# PWR_MGMT.net
KiCad netlist of a schematic drawn in Altium Designer
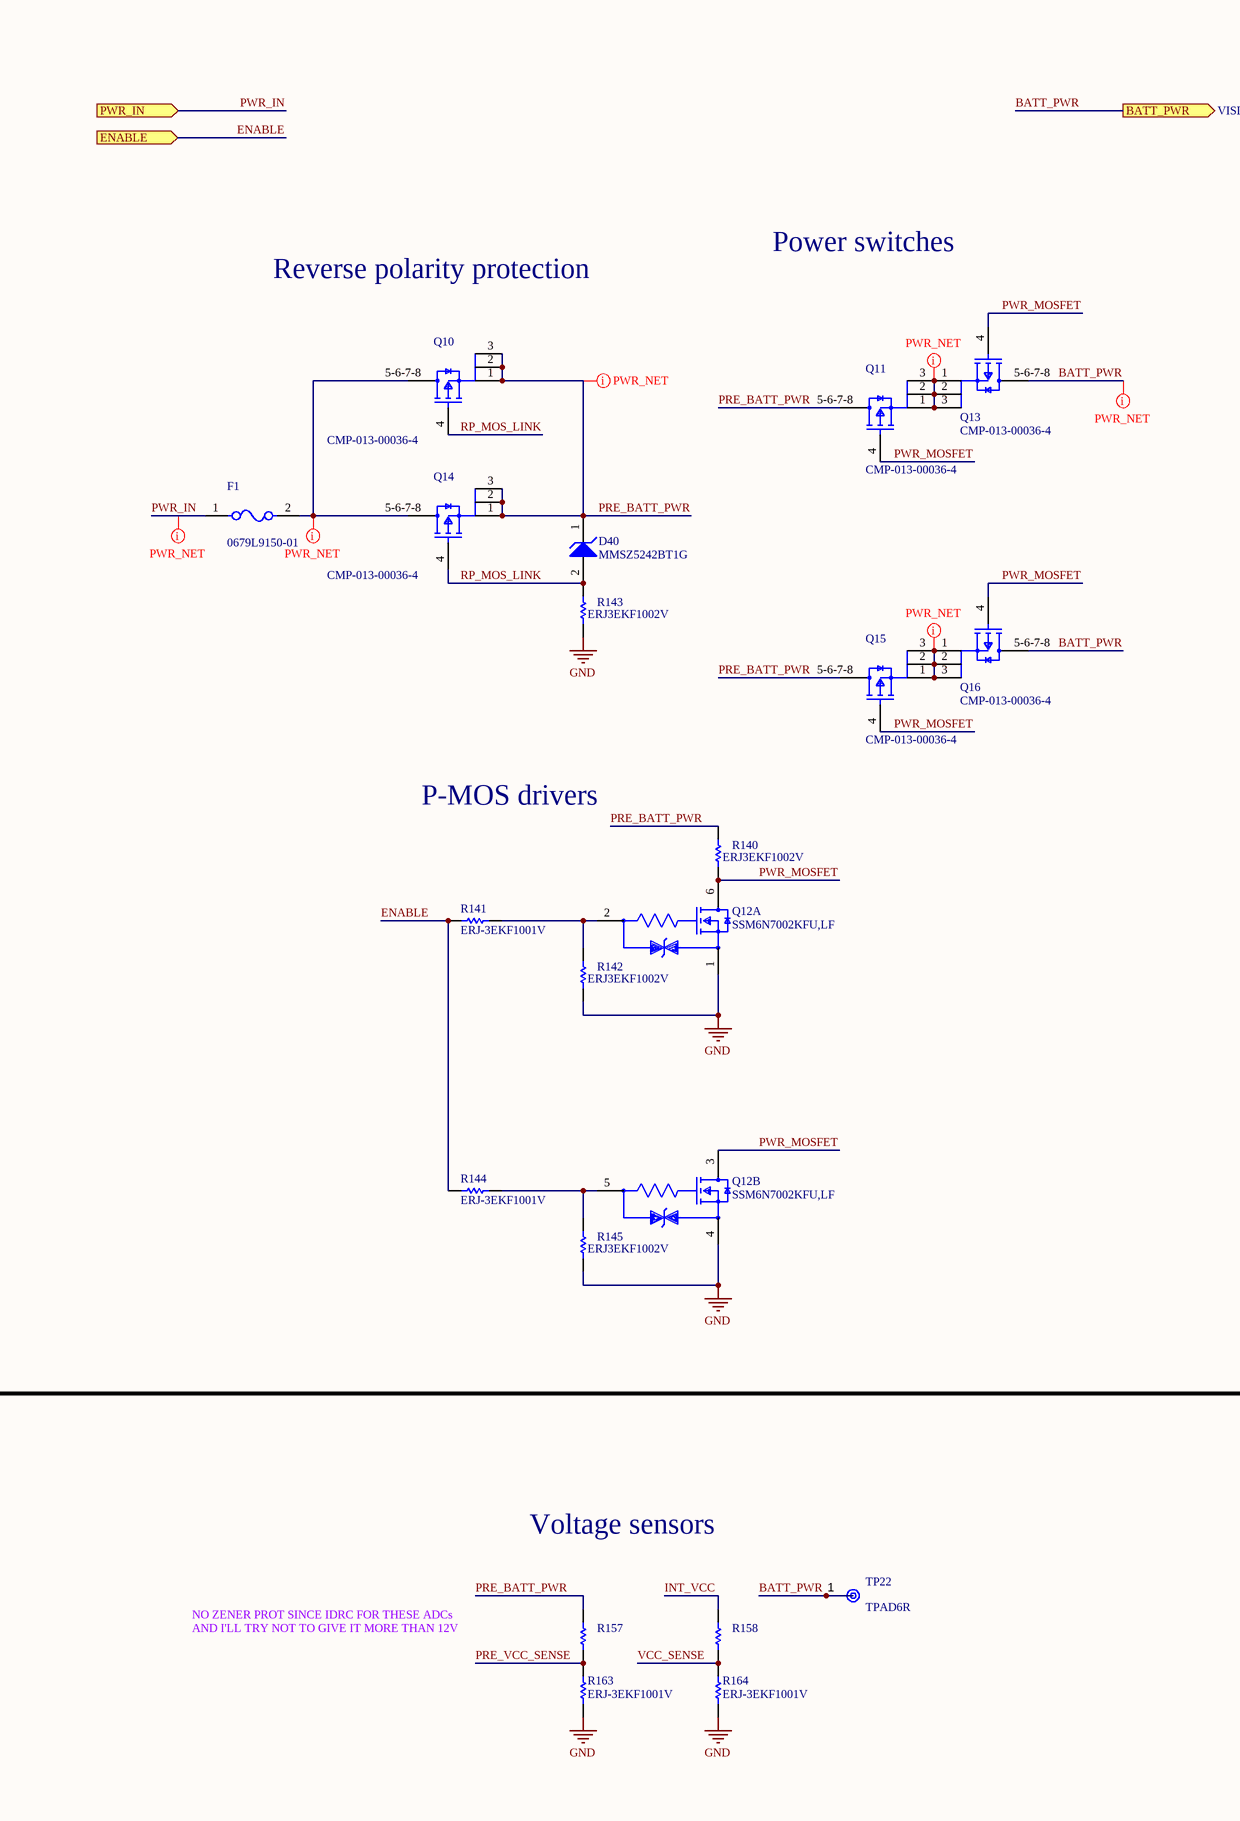
[diagram p0: PWR_MGMT.SchDoc, left]
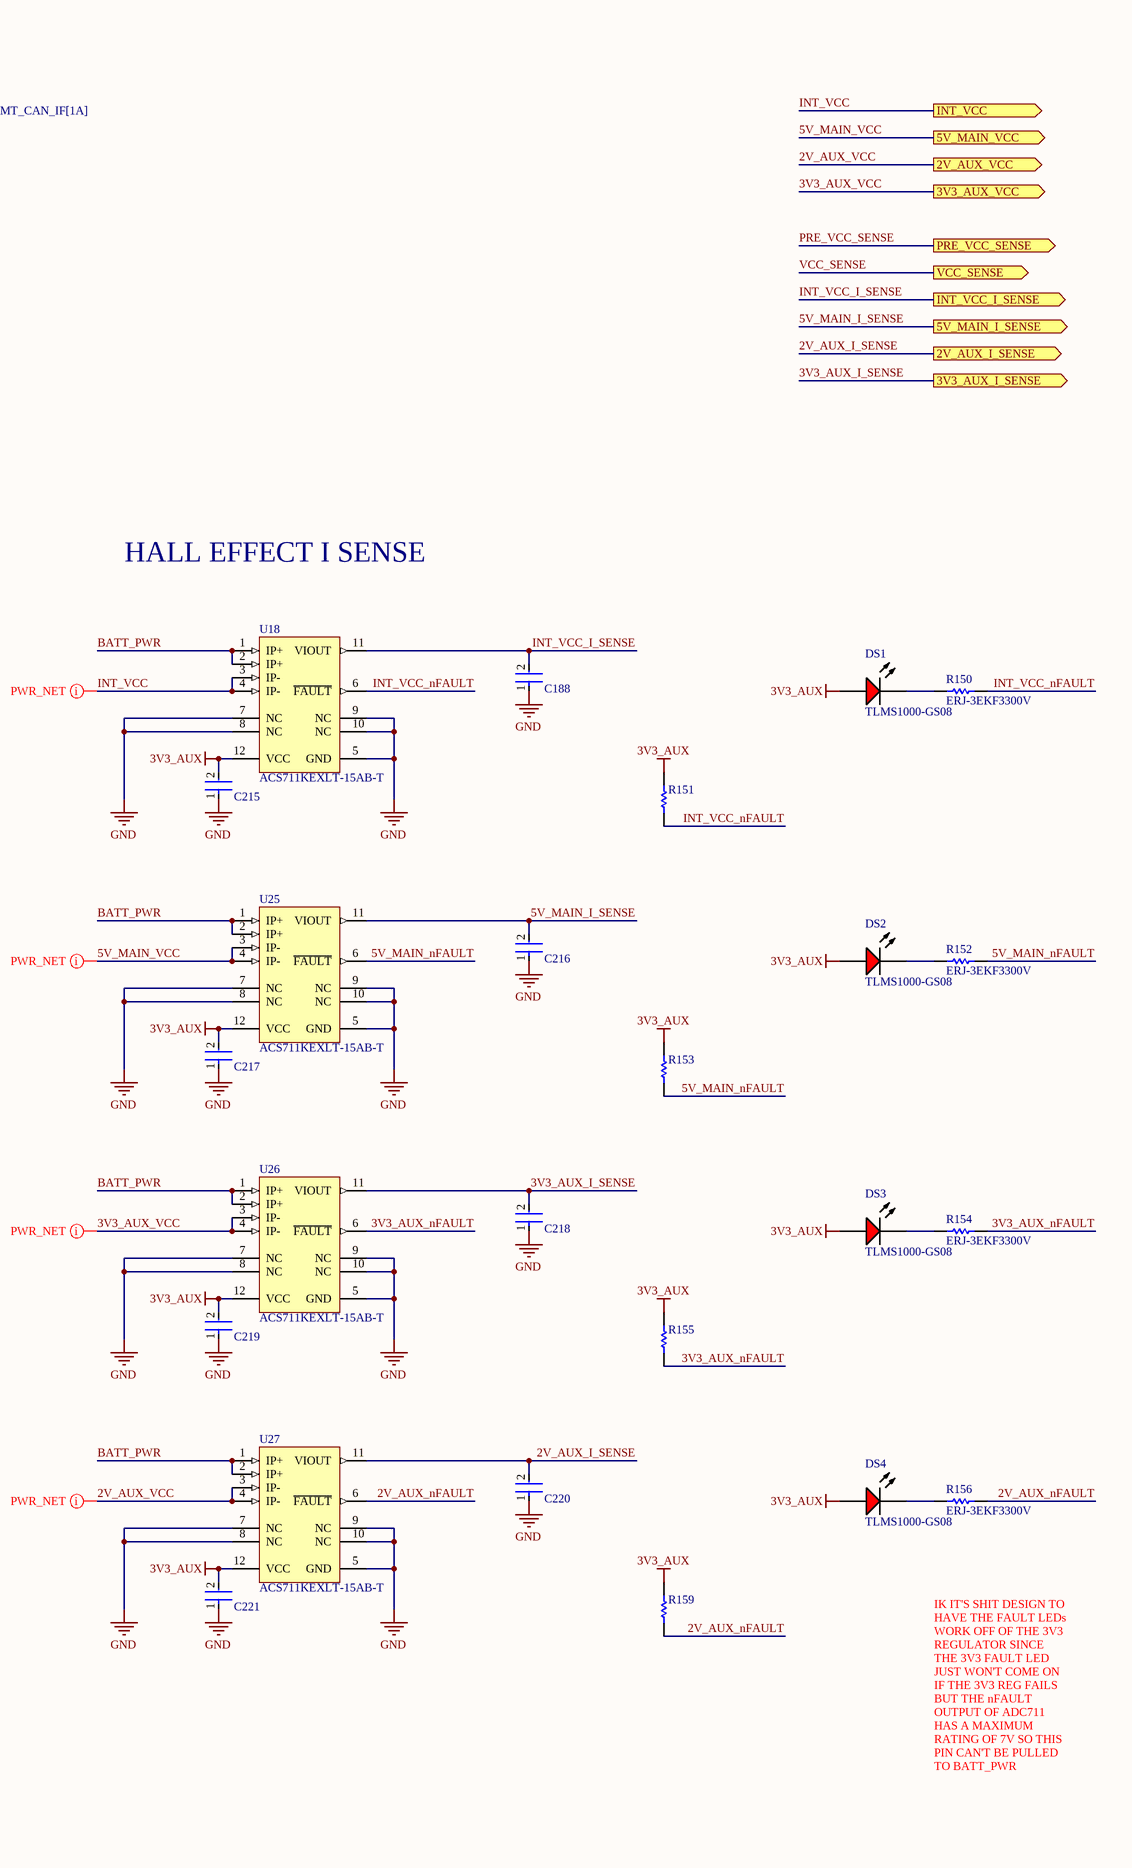
[diagram p1: PWR_MGMT.SchDoc, right]

(export (version "E")
  (design (tool "Eeschema 10.0.6"))
  (components
    (comp (ref "C188")
      (value "C0402C104K8PACTU")
      (footprint "FP-C0402-BB-MFG")
      (description "CAP CER 0.1UF 10V X5R 0402")
      (fields (field (name "MANUFACTURER") "Kemet") (field (name "TOLERANCE") "0.1"))
      (libsource (lib "Altium Content Vault") (part "b4654b650e69147ec39a6b967a45e02"))
    )
    (comp (ref "C215")
      (value "C0402C104K8PACTU")
      (footprint "FP-C0402-BB-MFG")
      (description "CAP CER 0.1UF 10V X5R 0402")
      (fields (field (name "MANUFACTURER") "Kemet") (field (name "TOLERANCE") "0.1"))
      (libsource (lib "Altium Content Vault") (part "b4654b650e69147ec39a6b967a45e02"))
    )
    (comp (ref "C216")
      (value "C0402C104K8PACTU")
      (footprint "FP-C0402-BB-MFG")
      (description "CAP CER 0.1UF 10V X5R 0402")
      (fields (field (name "MANUFACTURER") "Kemet") (field (name "TOLERANCE") "0.1"))
      (libsource (lib "Altium Content Vault") (part "b4654b650e69147ec39a6b967a45e02"))
    )
    (comp (ref "C217")
      (value "C0402C104K8PACTU")
      (footprint "FP-C0402-BB-MFG")
      (description "CAP CER 0.1UF 10V X5R 0402")
      (fields (field (name "MANUFACTURER") "Kemet") (field (name "TOLERANCE") "0.1"))
      (libsource (lib "Altium Content Vault") (part "b4654b650e69147ec39a6b967a45e02"))
    )
    (comp (ref "C218")
      (value "C0402C104K8PACTU")
      (footprint "FP-C0402-BB-MFG")
      (description "CAP CER 0.1UF 10V X5R 0402")
      (fields (field (name "MANUFACTURER") "Kemet") (field (name "TOLERANCE") "0.1"))
      (libsource (lib "Altium Content Vault") (part "b4654b650e69147ec39a6b967a45e02"))
    )
    (comp (ref "C219")
      (value "C0402C104K8PACTU")
      (footprint "FP-C0402-BB-MFG")
      (description "CAP CER 0.1UF 10V X5R 0402")
      (fields (field (name "MANUFACTURER") "Kemet") (field (name "TOLERANCE") "0.1"))
      (libsource (lib "Altium Content Vault") (part "b4654b650e69147ec39a6b967a45e02"))
    )
    (comp (ref "C220")
      (value "C0402C104K8PACTU")
      (footprint "FP-C0402-BB-MFG")
      (description "CAP CER 0.1UF 10V X5R 0402")
      (fields (field (name "MANUFACTURER") "Kemet") (field (name "TOLERANCE") "0.1"))
      (libsource (lib "Altium Content Vault") (part "b4654b650e69147ec39a6b967a45e02"))
    )
    (comp (ref "C221")
      (value "C0402C104K8PACTU")
      (footprint "FP-C0402-BB-MFG")
      (description "CAP CER 0.1UF 10V X5R 0402")
      (fields (field (name "MANUFACTURER") "Kemet") (field (name "TOLERANCE") "0.1"))
      (libsource (lib "Altium Content Vault") (part "b4654b650e69147ec39a6b967a45e02"))
    )
    (comp (ref "D40")
      (value "MMSZ5242BT1G")
      (footprint "ONSC-SOD-123-2-425-04_V")
      (description "Zener Voltage Regulator, 500 mW, 2-Pin SOD-123, Pb-Free, Tape and Reel")
      (fields (field (name "MANUFACTURER") "On Semiconductor"))
      (libsource (lib "Altium Content Vault") (part "ONSC-K1A2-2"))
    )
    (comp (ref "DS1")
      (value "TLMS1000-GS08")
      (footprint "VISH-TLMS1000_V")
      (description "Low Current LED, 40 mW, 1.8 V, -40 to 100 degC, 2-Pin SMD (0603), RoHS, Tape and Reel")
      (fields (field (name "MANUFACTURER") "Vishay"))
      (libsource (lib "Altium Content Vault") (part "LED-RED-AK-2"))
    )
    (comp (ref "DS2")
      (value "TLMS1000-GS08")
      (footprint "VISH-TLMS1000_V")
      (description "Low Current LED, 40 mW, 1.8 V, -40 to 100 degC, 2-Pin SMD (0603), RoHS, Tape and Reel")
      (fields (field (name "MANUFACTURER") "Vishay"))
      (libsource (lib "Altium Content Vault") (part "LED-RED-AK-2"))
    )
    (comp (ref "DS3")
      (value "TLMS1000-GS08")
      (footprint "VISH-TLMS1000_V")
      (description "Low Current LED, 40 mW, 1.8 V, -40 to 100 degC, 2-Pin SMD (0603), RoHS, Tape and Reel")
      (fields (field (name "MANUFACTURER") "Vishay"))
      (libsource (lib "Altium Content Vault") (part "LED-RED-AK-2"))
    )
    (comp (ref "DS4")
      (value "TLMS1000-GS08")
      (footprint "VISH-TLMS1000_V")
      (description "Low Current LED, 40 mW, 1.8 V, -40 to 100 degC, 2-Pin SMD (0603), RoHS, Tape and Reel")
      (fields (field (name "MANUFACTURER") "Vishay"))
      (libsource (lib "Altium Content Vault") (part "LED-RED-AK-2"))
    )
    (comp (ref "F1")
      (value "0679L9150-01")
      (footprint "FP-0679L-MFG")
      (description "FUSE BRD MNT 15A 125VAC/VDC")
      (fields
        (field (name "OCTOPART") "https://octopart.com/0679l9150-01-bel+fuse-70850665")
        (field (name "MANUFACTURER") "Bel Fuse")
      )
      (libsource (lib "Altium Content Vault") (part "5bcf9b9f640e542cf0359d10258e979"))
    )
    (comp (ref "Q10")
      (value "CMP-013-00036-4")
      (footprint "SISH615ADN-T1-GE3-Footprint-1")
      (description "Trans MOSFET P-CH 20V 22.1A 8-Pin PowerPAK 1212 EP T/R")
      (libsource (lib "Space Concordia") (part "CMP-013-00036-4"))
    )
    (comp (ref "Q11")
      (value "CMP-013-00036-4")
      (footprint "SISH615ADN-T1-GE3-Footprint-1")
      (description "Trans MOSFET P-CH 20V 22.1A 8-Pin PowerPAK 1212 EP T/R")
      (libsource (lib "Space Concordia") (part "CMP-013-00036-4"))
    )
    (comp (ref "Q12")
      (value "SSM6N7002KFU,LF")
      (footprint "FP-SSOP6-P-0_65A-MFG")
      (description "MOSFET 2N-CH 60V 0.3A")
      (libsource (lib "Altium Content Vault") (part "088aa6ac103fdeebe0d1c52ece6b7b9"))
    )
    (comp (ref "Q13")
      (value "CMP-013-00036-4")
      (footprint "SISH615ADN-T1-GE3-Footprint-1")
      (description "Trans MOSFET P-CH 20V 22.1A 8-Pin PowerPAK 1212 EP T/R")
      (libsource (lib "Space Concordia") (part "CMP-013-00036-4"))
    )
    (comp (ref "Q14")
      (value "CMP-013-00036-4")
      (footprint "SISH615ADN-T1-GE3-Footprint-1")
      (description "Trans MOSFET P-CH 20V 22.1A 8-Pin PowerPAK 1212 EP T/R")
      (libsource (lib "Space Concordia") (part "CMP-013-00036-4"))
    )
    (comp (ref "Q15")
      (value "CMP-013-00036-4")
      (footprint "SISH615ADN-T1-GE3-Footprint-1")
      (description "Trans MOSFET P-CH 20V 22.1A 8-Pin PowerPAK 1212 EP T/R")
      (libsource (lib "Space Concordia") (part "CMP-013-00036-4"))
    )
    (comp (ref "Q16")
      (value "CMP-013-00036-4")
      (footprint "SISH615ADN-T1-GE3-Footprint-1")
      (description "Trans MOSFET P-CH 20V 22.1A 8-Pin PowerPAK 1212 EP T/R")
      (libsource (lib "Space Concordia") (part "CMP-013-00036-4"))
    )
    (comp (ref "R140")
      (value "ERJ3EKF1002V")
      (footprint "RESC1609X55X30LL15T15")
      (description "Chip Resistor, 10 KOhm, +/- 1%, 0.1 W, -55 to 155 degC, 0603 (1608 Metric), RoHS, Tape and Reel")
      (fields (field (name "TOLERANCE") "1%") (field (name "MANUFACTURER") "Panasonic"))
      (libsource (lib "Altium Content Vault") (part "RES-2"))
    )
    (comp (ref "R141")
      (value "ERJ-3EKF1001V")
      (footprint "RESC1608X55X30LL15T15")
      (fields (field (name "MANUFACTURER") "Panasonic"))
      (libsource (lib "Altium Content Vault") (part "RES"))
    )
    (comp (ref "R142")
      (value "ERJ3EKF1002V")
      (footprint "RESC1609X55X30LL15T15")
      (description "Chip Resistor, 10 KOhm, +/- 1%, 0.1 W, -55 to 155 degC, 0603 (1608 Metric), RoHS, Tape and Reel")
      (fields (field (name "TOLERANCE") "1%") (field (name "MANUFACTURER") "Panasonic"))
      (libsource (lib "Altium Content Vault") (part "RES-2"))
    )
    (comp (ref "R143")
      (value "ERJ3EKF1002V")
      (footprint "RESC1609X55X30LL15T15")
      (description "Chip Resistor, 10 KOhm, +/- 1%, 0.1 W, -55 to 155 degC, 0603 (1608 Metric), RoHS, Tape and Reel")
      (fields (field (name "TOLERANCE") "1%") (field (name "MANUFACTURER") "Panasonic"))
      (libsource (lib "Altium Content Vault") (part "RES-2"))
    )
    (comp (ref "R144")
      (value "ERJ-3EKF1001V")
      (footprint "RESC1608X55X30LL15T15")
      (fields (field (name "MANUFACTURER") "Panasonic"))
      (libsource (lib "Altium Content Vault") (part "RES"))
    )
    (comp (ref "R145")
      (value "ERJ3EKF1002V")
      (footprint "RESC1609X55X30LL15T15")
      (description "Chip Resistor, 10 KOhm, +/- 1%, 0.1 W, -55 to 155 degC, 0603 (1608 Metric), RoHS, Tape and Reel")
      (fields (field (name "TOLERANCE") "1%") (field (name "MANUFACTURER") "Panasonic"))
      (libsource (lib "Altium Content Vault") (part "RES-2"))
    )
    (comp (ref "R150")
      (value "ERJ-3EKF3300V")
      (footprint "RESC1608X55X30LL15T15")
      (description "Chip Resistor, 330 Ohm, +/- 1%, 0.1 W, -55 to 155 degC, 0603 (1608 Metric), RoHS, Tape and Reel")
      (libsource (lib "Altium Content Vault") (part "RES-2"))
    )
    (comp (ref "R151")
      (value "ERJ3EKF1002V")
      (footprint "RESC1609X55X30LL15T15")
      (description "Chip Resistor, 10 KOhm, +/- 1%, 0.1 W, -55 to 155 degC, 0603 (1608 Metric), RoHS, Tape and Reel")
      (fields (field (name "TOLERANCE") "1%") (field (name "MANUFACTURER") "Panasonic"))
      (libsource (lib "Altium Content Vault") (part "RES-2"))
    )
    (comp (ref "R152")
      (value "ERJ-3EKF3300V")
      (footprint "RESC1608X55X30LL15T15")
      (description "Chip Resistor, 330 Ohm, +/- 1%, 0.1 W, -55 to 155 degC, 0603 (1608 Metric), RoHS, Tape and Reel")
      (libsource (lib "Altium Content Vault") (part "RES-2"))
    )
    (comp (ref "R153")
      (value "ERJ3EKF1002V")
      (footprint "RESC1609X55X30LL15T15")
      (description "Chip Resistor, 10 KOhm, +/- 1%, 0.1 W, -55 to 155 degC, 0603 (1608 Metric), RoHS, Tape and Reel")
      (fields (field (name "TOLERANCE") "1%") (field (name "MANUFACTURER") "Panasonic"))
      (libsource (lib "Altium Content Vault") (part "RES-2"))
    )
    (comp (ref "R154")
      (value "ERJ-3EKF3300V")
      (footprint "RESC1608X55X30LL15T15")
      (description "Chip Resistor, 330 Ohm, +/- 1%, 0.1 W, -55 to 155 degC, 0603 (1608 Metric), RoHS, Tape and Reel")
      (libsource (lib "Altium Content Vault") (part "RES-2"))
    )
    (comp (ref "R155")
      (value "ERJ3EKF1002V")
      (footprint "RESC1609X55X30LL15T15")
      (description "Chip Resistor, 10 KOhm, +/- 1%, 0.1 W, -55 to 155 degC, 0603 (1608 Metric), RoHS, Tape and Reel")
      (fields (field (name "TOLERANCE") "1%") (field (name "MANUFACTURER") "Panasonic"))
      (libsource (lib "Altium Content Vault") (part "RES-2"))
    )
    (comp (ref "R156")
      (value "ERJ-3EKF3300V")
      (footprint "RESC1608X55X30LL15T15")
      (description "Chip Resistor, 330 Ohm, +/- 1%, 0.1 W, -55 to 155 degC, 0603 (1608 Metric), RoHS, Tape and Reel")
      (libsource (lib "Altium Content Vault") (part "RES-2"))
    )
    (comp (ref "R157")
      (value "ERJ3EKF1002V")
      (footprint "RESC1609X55X30LL15T15")
      (description "Chip Resistor, 10 KOhm, +/- 1%, 0.1 W, -55 to 155 degC, 0603 (1608 Metric), RoHS, Tape and Reel")
      (fields (field (name "TOLERANCE") "1%") (field (name "MANUFACTURER") "Panasonic"))
      (libsource (lib "Altium Content Vault") (part "RES-2"))
    )
    (comp (ref "R158")
      (value "ERJ3EKF1002V")
      (footprint "RESC1609X55X30LL15T15")
      (description "Chip Resistor, 10 KOhm, +/- 1%, 0.1 W, -55 to 155 degC, 0603 (1608 Metric), RoHS, Tape and Reel")
      (fields (field (name "TOLERANCE") "1%") (field (name "MANUFACTURER") "Panasonic"))
      (libsource (lib "Altium Content Vault") (part "RES-2"))
    )
    (comp (ref "R159")
      (value "ERJ3EKF1002V")
      (footprint "RESC1609X55X30LL15T15")
      (description "Chip Resistor, 10 KOhm, +/- 1%, 0.1 W, -55 to 155 degC, 0603 (1608 Metric), RoHS, Tape and Reel")
      (fields (field (name "TOLERANCE") "1%") (field (name "MANUFACTURER") "Panasonic"))
      (libsource (lib "Altium Content Vault") (part "RES-2"))
    )
    (comp (ref "R163")
      (value "ERJ-3EKF1001V")
      (footprint "RESC1608X55X30LL15T15")
      (fields (field (name "MANUFACTURER") "Panasonic"))
      (libsource (lib "Altium Content Vault") (part "RES"))
    )
    (comp (ref "R164")
      (value "ERJ-3EKF1001V")
      (footprint "RESC1608X55X30LL15T15")
      (fields (field (name "MANUFACTURER") "Panasonic"))
      (libsource (lib "Altium Content Vault") (part "RES"))
    )
    (comp (ref "TP22")
      (value "TPAD6R")
      (footprint "New footprint 1")
      (description "Test Point .6mm")
      (libsource (lib "Space Concordia") (part "TP"))
    )
    (comp (ref "U18")
      (value "ACS711KEXLT-15AB-T")
      (footprint "ALEG-EX-12_V")
      (libsource (lib "Altium Content Vault") (part "ALEG-ACS711-QFN-12"))
    )
    (comp (ref "U25")
      (value "ACS711KEXLT-15AB-T")
      (footprint "ALEG-EX-12_V")
      (libsource (lib "Altium Content Vault") (part "ALEG-ACS711-QFN-12"))
    )
    (comp (ref "U26")
      (value "ACS711KEXLT-15AB-T")
      (footprint "ALEG-EX-12_V")
      (libsource (lib "Altium Content Vault") (part "ALEG-ACS711-QFN-12"))
    )
    (comp (ref "U27")
      (value "ACS711KEXLT-15AB-T")
      (footprint "ALEG-EX-12_V")
      (libsource (lib "Altium Content Vault") (part "ALEG-ACS711-QFN-12"))
    )
  )
  (nets
    (net (code "1") (name "/2V_AUX_I_SENSE") (class "Default")
      (node (ref "C220") (pin "2") (pinfunction "2_2") (pintype "passive"))
      (node (ref "U27") (pin "11") (pinfunction "VIOUT_11") (pintype "output"))
    )
    (net (code "2") (name "/2V_AUX_VCC") (class "Default")
      (node (ref "U27") (pin "3") (pinfunction "IP-_3") (pintype "input"))
      (node (ref "U27") (pin "4") (pinfunction "IP-_4") (pintype "input"))
    )
    (net (code "3") (name "/2V_AUX_nFAULT") (class "Default")
      (node (ref "R156") (pin "2") (pinfunction "2_2") (pintype "passive"))
      (node (ref "R159") (pin "1") (pinfunction "1_1") (pintype "passive"))
      (node (ref "U27") (pin "6") (pinfunction "~{FAULT}_6") (pintype "output"))
    )
    (net (code "4") (name "/3V3_AUX_I_SENSE") (class "Default")
      (node (ref "C218") (pin "2") (pinfunction "2_2") (pintype "passive"))
      (node (ref "U26") (pin "11") (pinfunction "VIOUT_11") (pintype "output"))
    )
    (net (code "5") (name "/3V3_AUX_VCC") (class "Default")
      (node (ref "U26") (pin "3") (pinfunction "IP-_3") (pintype "input"))
      (node (ref "U26") (pin "4") (pinfunction "IP-_4") (pintype "input"))
    )
    (net (code "6") (name "/3V3_AUX_nFAULT") (class "Default")
      (node (ref "R154") (pin "2") (pinfunction "2_2") (pintype "passive"))
      (node (ref "R155") (pin "1") (pinfunction "1_1") (pintype "passive"))
      (node (ref "U26") (pin "6") (pinfunction "~{FAULT}_6") (pintype "output"))
    )
    (net (code "7") (name "/5V_MAIN_I_SENSE") (class "Default")
      (node (ref "C216") (pin "2") (pinfunction "2_2") (pintype "passive"))
      (node (ref "U25") (pin "11") (pinfunction "VIOUT_11") (pintype "output"))
    )
    (net (code "8") (name "/5V_MAIN_VCC") (class "Default")
      (node (ref "U25") (pin "3") (pinfunction "IP-_3") (pintype "input"))
      (node (ref "U25") (pin "4") (pinfunction "IP-_4") (pintype "input"))
    )
    (net (code "9") (name "/5V_MAIN_nFAULT") (class "Default")
      (node (ref "R152") (pin "2") (pinfunction "2_2") (pintype "passive"))
      (node (ref "R153") (pin "1") (pinfunction "1_1") (pintype "passive"))
      (node (ref "U25") (pin "6") (pinfunction "~{FAULT}_6") (pintype "output"))
    )
    (net (code "10") (name "/BATT_PWR") (class "Default")
      (node (ref "Q13") (pin "5-6-7-8") (pinfunction "D_5-6-7-8") (pintype "passive"))
      (node (ref "Q16") (pin "5-6-7-8") (pinfunction "D_5-6-7-8") (pintype "passive"))
      (node (ref "TP22") (pin "1") (pinfunction "TP_1") (pintype "passive"))
      (node (ref "U18") (pin "1") (pinfunction "IP+_1") (pintype "input"))
      (node (ref "U18") (pin "2") (pinfunction "IP+_2") (pintype "input"))
      (node (ref "U25") (pin "1") (pinfunction "IP+_1") (pintype "input"))
      (node (ref "U25") (pin "2") (pinfunction "IP+_2") (pintype "input"))
      (node (ref "U26") (pin "1") (pinfunction "IP+_1") (pintype "input"))
      (node (ref "U26") (pin "2") (pinfunction "IP+_2") (pintype "input"))
      (node (ref "U27") (pin "1") (pinfunction "IP+_1") (pintype "input"))
      (node (ref "U27") (pin "2") (pinfunction "IP+_2") (pintype "input"))
    )
    (net (code "11") (name "/ENABLE") (class "Default")
      (node (ref "R141") (pin "1") (pinfunction "1_1") (pintype "passive"))
      (node (ref "R144") (pin "1") (pinfunction "1_1") (pintype "passive"))
    )
    (net (code "12") (name "/INT_VCC") (class "Default")
      (node (ref "R158") (pin "1") (pinfunction "1_1") (pintype "passive"))
      (node (ref "U18") (pin "3") (pinfunction "IP-_3") (pintype "input"))
      (node (ref "U18") (pin "4") (pinfunction "IP-_4") (pintype "input"))
    )
    (net (code "13") (name "/INT_VCC_I_SENSE") (class "Default")
      (node (ref "C188") (pin "2") (pinfunction "2_2") (pintype "passive"))
      (node (ref "U18") (pin "11") (pinfunction "VIOUT_11") (pintype "output"))
    )
    (net (code "14") (name "/INT_VCC_nFAULT") (class "Default")
      (node (ref "R150") (pin "2") (pinfunction "2_2") (pintype "passive"))
      (node (ref "R151") (pin "1") (pinfunction "1_1") (pintype "passive"))
      (node (ref "U18") (pin "6") (pinfunction "~{FAULT}_6") (pintype "output"))
    )
    (net (code "15") (name "/PRE_BATT_PWR") (class "Default")
      (node (ref "D40") (pin "1") (pinfunction "K_1") (pintype "passive"))
      (node (ref "Q10") (pin "1") (pinfunction "S_1") (pintype "passive"))
      (node (ref "Q10") (pin "2") (pinfunction "S_2") (pintype "passive"))
      (node (ref "Q10") (pin "3") (pinfunction "S_3") (pintype "passive"))
      (node (ref "Q11") (pin "5-6-7-8") (pinfunction "D_5-6-7-8") (pintype "passive"))
      (node (ref "Q14") (pin "1") (pinfunction "S_1") (pintype "passive"))
      (node (ref "Q14") (pin "2") (pinfunction "S_2") (pintype "passive"))
      (node (ref "Q14") (pin "3") (pinfunction "S_3") (pintype "passive"))
      (node (ref "Q15") (pin "5-6-7-8") (pinfunction "D_5-6-7-8") (pintype "passive"))
      (node (ref "R140") (pin "1") (pinfunction "1_1") (pintype "passive"))
      (node (ref "R157") (pin "1") (pinfunction "1_1") (pintype "passive"))
    )
    (net (code "16") (name "/PRE_VCC_SENSE") (class "Default")
      (node (ref "R157") (pin "2") (pinfunction "2_2") (pintype "passive"))
      (node (ref "R163") (pin "2") (pinfunction "2_2") (pintype "passive"))
    )
    (net (code "17") (name "/PWR_IN") (class "Default")
      (node (ref "F1") (pin "1") (pinfunction "1_1") (pintype "passive"))
    )
    (net (code "18") (name "/PWR_MOSFET") (class "Default")
      (node (ref "Q11") (pin "4") (pinfunction "G_4") (pintype "passive"))
      (node (ref "Q12") (pin "3") (pinfunction "Drain2_3") (pintype "passive"))
      (node (ref "Q12") (pin "6") (pinfunction "Drain1_6") (pintype "passive"))
      (node (ref "Q13") (pin "4") (pinfunction "G_4") (pintype "passive"))
      (node (ref "Q15") (pin "4") (pinfunction "G_4") (pintype "passive"))
      (node (ref "Q16") (pin "4") (pinfunction "G_4") (pintype "passive"))
      (node (ref "R140") (pin "2") (pinfunction "2_2") (pintype "passive"))
    )
    (net (code "19") (name "/RP_MOS_LINK") (class "Default")
      (node (ref "D40") (pin "2") (pinfunction "A_2") (pintype "passive"))
      (node (ref "Q10") (pin "4") (pinfunction "G_4") (pintype "passive"))
      (node (ref "Q14") (pin "4") (pinfunction "G_4") (pintype "passive"))
      (node (ref "R143") (pin "1") (pinfunction "1_1") (pintype "passive"))
    )
    (net (code "20") (name "/VCC_SENSE") (class "Default")
      (node (ref "R158") (pin "2") (pinfunction "2_2") (pintype "passive"))
      (node (ref "R164") (pin "2") (pinfunction "2_2") (pintype "passive"))
    )
    (net (code "21") (name "3V3_AUX") (class "Default")
      (node (ref "C215") (pin "2") (pinfunction "2_2") (pintype "passive"))
      (node (ref "C217") (pin "2") (pinfunction "2_2") (pintype "passive"))
      (node (ref "C219") (pin "2") (pinfunction "2_2") (pintype "passive"))
      (node (ref "C221") (pin "2") (pinfunction "2_2") (pintype "passive"))
      (node (ref "DS1") (pin "1") (pinfunction "A_1") (pintype "passive"))
      (node (ref "DS2") (pin "1") (pinfunction "A_1") (pintype "passive"))
      (node (ref "DS3") (pin "1") (pinfunction "A_1") (pintype "passive"))
      (node (ref "DS4") (pin "1") (pinfunction "A_1") (pintype "passive"))
      (node (ref "R151") (pin "2") (pinfunction "2_2") (pintype "passive"))
      (node (ref "R153") (pin "2") (pinfunction "2_2") (pintype "passive"))
      (node (ref "R155") (pin "2") (pinfunction "2_2") (pintype "passive"))
      (node (ref "R159") (pin "2") (pinfunction "2_2") (pintype "passive"))
      (node (ref "U18") (pin "12") (pinfunction "VCC_12") (pintype "power_in"))
      (node (ref "U25") (pin "12") (pinfunction "VCC_12") (pintype "power_in"))
      (node (ref "U26") (pin "12") (pinfunction "VCC_12") (pintype "power_in"))
      (node (ref "U27") (pin "12") (pinfunction "VCC_12") (pintype "power_in"))
    )
    (net (code "22") (name "GND") (class "Default")
      (node (ref "C188") (pin "1") (pinfunction "1_1") (pintype "passive"))
      (node (ref "C215") (pin "1") (pinfunction "1_1") (pintype "passive"))
      (node (ref "C216") (pin "1") (pinfunction "1_1") (pintype "passive"))
      (node (ref "C217") (pin "1") (pinfunction "1_1") (pintype "passive"))
      (node (ref "C218") (pin "1") (pinfunction "1_1") (pintype "passive"))
      (node (ref "C219") (pin "1") (pinfunction "1_1") (pintype "passive"))
      (node (ref "C220") (pin "1") (pinfunction "1_1") (pintype "passive"))
      (node (ref "C221") (pin "1") (pinfunction "1_1") (pintype "passive"))
      (node (ref "Q12") (pin "1") (pinfunction "Source1_1") (pintype "passive"))
      (node (ref "Q12") (pin "4") (pinfunction "Source2_4") (pintype "passive"))
      (node (ref "R142") (pin "2") (pinfunction "2_2") (pintype "passive"))
      (node (ref "R143") (pin "2") (pinfunction "2_2") (pintype "passive"))
      (node (ref "R145") (pin "2") (pinfunction "2_2") (pintype "passive"))
      (node (ref "R163") (pin "1") (pinfunction "1_1") (pintype "passive"))
      (node (ref "R164") (pin "1") (pinfunction "1_1") (pintype "passive"))
      (node (ref "U18") (pin "10") (pinfunction "NC_10") (pintype "passive"))
      (node (ref "U18") (pin "5") (pinfunction "GND_5") (pintype "power_in"))
      (node (ref "U18") (pin "7") (pinfunction "NC_7") (pintype "passive"))
      (node (ref "U18") (pin "8") (pinfunction "NC_8") (pintype "passive"))
      (node (ref "U18") (pin "9") (pinfunction "NC_9") (pintype "passive"))
      (node (ref "U25") (pin "10") (pinfunction "NC_10") (pintype "passive"))
      (node (ref "U25") (pin "5") (pinfunction "GND_5") (pintype "power_in"))
      (node (ref "U25") (pin "7") (pinfunction "NC_7") (pintype "passive"))
      (node (ref "U25") (pin "8") (pinfunction "NC_8") (pintype "passive"))
      (node (ref "U25") (pin "9") (pinfunction "NC_9") (pintype "passive"))
      (node (ref "U26") (pin "10") (pinfunction "NC_10") (pintype "passive"))
      (node (ref "U26") (pin "5") (pinfunction "GND_5") (pintype "power_in"))
      (node (ref "U26") (pin "7") (pinfunction "NC_7") (pintype "passive"))
      (node (ref "U26") (pin "8") (pinfunction "NC_8") (pintype "passive"))
      (node (ref "U26") (pin "9") (pinfunction "NC_9") (pintype "passive"))
      (node (ref "U27") (pin "10") (pinfunction "NC_10") (pintype "passive"))
      (node (ref "U27") (pin "5") (pinfunction "GND_5") (pintype "power_in"))
      (node (ref "U27") (pin "7") (pinfunction "NC_7") (pintype "passive"))
      (node (ref "U27") (pin "8") (pinfunction "NC_8") (pintype "passive"))
      (node (ref "U27") (pin "9") (pinfunction "NC_9") (pintype "passive"))
    )
    (net (code "23") (name "Net-(DS1-K)") (class "Default")
      (node (ref "DS1") (pin "2") (pinfunction "K_2") (pintype "passive"))
      (node (ref "R150") (pin "1") (pinfunction "1_1") (pintype "passive"))
    )
    (net (code "24") (name "Net-(DS2-K)") (class "Default")
      (node (ref "DS2") (pin "2") (pinfunction "K_2") (pintype "passive"))
      (node (ref "R152") (pin "1") (pinfunction "1_1") (pintype "passive"))
    )
    (net (code "25") (name "Net-(DS3-K)") (class "Default")
      (node (ref "DS3") (pin "2") (pinfunction "K_2") (pintype "passive"))
      (node (ref "R154") (pin "1") (pinfunction "1_1") (pintype "passive"))
    )
    (net (code "26") (name "Net-(DS4-K)") (class "Default")
      (node (ref "DS4") (pin "2") (pinfunction "K_2") (pintype "passive"))
      (node (ref "R156") (pin "1") (pinfunction "1_1") (pintype "passive"))
    )
    (net (code "27") (name "Net-(Q10-D)") (class "Default")
      (node (ref "F1") (pin "2") (pinfunction "2_2") (pintype "passive"))
      (node (ref "Q10") (pin "5-6-7-8") (pinfunction "D_5-6-7-8") (pintype "passive"))
      (node (ref "Q14") (pin "5-6-7-8") (pinfunction "D_5-6-7-8") (pintype "passive"))
    )
    (net (code "28") (name "Net-(Q11-S-Pad1)") (class "Default")
      (node (ref "Q11") (pin "1") (pinfunction "S_1") (pintype "passive"))
      (node (ref "Q11") (pin "2") (pinfunction "S_2") (pintype "passive"))
      (node (ref "Q11") (pin "3") (pinfunction "S_3") (pintype "passive"))
      (node (ref "Q13") (pin "1") (pinfunction "S_1") (pintype "passive"))
      (node (ref "Q13") (pin "2") (pinfunction "S_2") (pintype "passive"))
      (node (ref "Q13") (pin "3") (pinfunction "S_3") (pintype "passive"))
    )
    (net (code "29") (name "Net-(Q12A-Gate1)") (class "Default")
      (node (ref "Q12") (pin "2") (pinfunction "Gate1_2") (pintype "passive"))
      (node (ref "R141") (pin "2") (pinfunction "2_2") (pintype "passive"))
      (node (ref "R142") (pin "1") (pinfunction "1_1") (pintype "passive"))
    )
    (net (code "30") (name "Net-(Q12B-Gate2)") (class "Default")
      (node (ref "Q12") (pin "5") (pinfunction "Gate2_5") (pintype "passive"))
      (node (ref "R144") (pin "2") (pinfunction "2_2") (pintype "passive"))
      (node (ref "R145") (pin "1") (pinfunction "1_1") (pintype "passive"))
    )
    (net (code "31") (name "Net-(Q15-S-Pad1)") (class "Default")
      (node (ref "Q15") (pin "1") (pinfunction "S_1") (pintype "passive"))
      (node (ref "Q15") (pin "2") (pinfunction "S_2") (pintype "passive"))
      (node (ref "Q15") (pin "3") (pinfunction "S_3") (pintype "passive"))
      (node (ref "Q16") (pin "1") (pinfunction "S_1") (pintype "passive"))
      (node (ref "Q16") (pin "2") (pinfunction "S_2") (pintype "passive"))
      (node (ref "Q16") (pin "3") (pinfunction "S_3") (pintype "passive"))
    )
  )
)
